# FlashMemory.net
KiCad netlist of a schematic drawn in Altium Designer
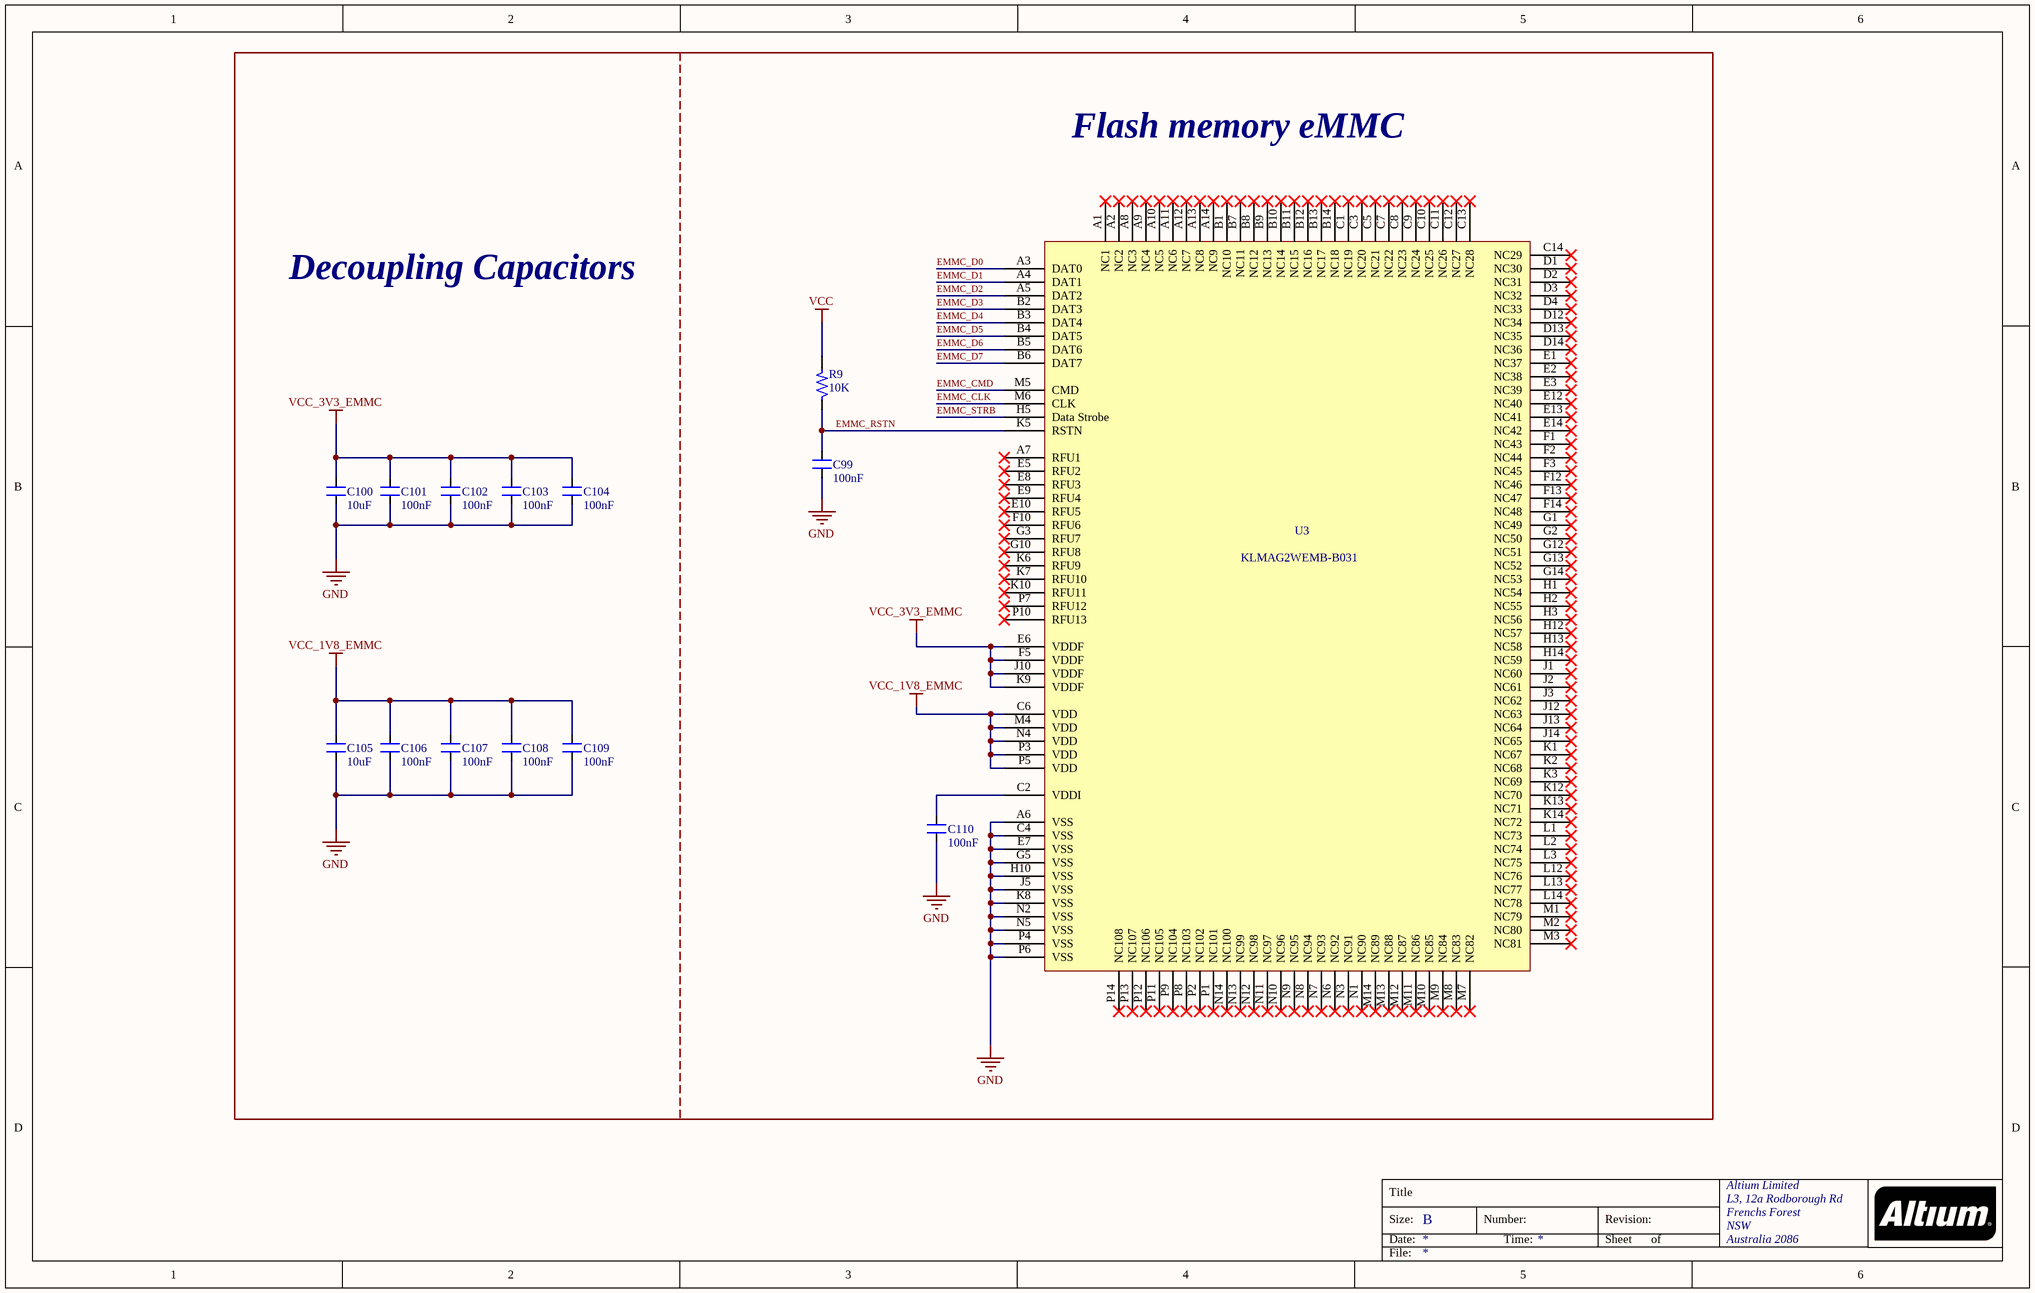
[diagram p0: FlashMemory.SchDoc]

(export (version "E")
  (design (tool "Eeschema 10.0.6"))
  (components
    (comp (ref "C99")
      (value "100nF")
      (footprint "CAP_0201")
      (description "0.1µF ±10% 25V Ceramic Capacitor X5R 0201 (0603 Metric)")
      (fields
        (field (name "MANUFACTURER") "TDK Corporation")
        (field (name "MANUFACTURER PART NUMBER") "C0603X5R1E104K030BB")
      )
      (libsource (lib "EsteemPCB_SOM_Course_intlib") (part "CAP_100nF-25V-10%-0201"))
    )
    (comp (ref "C100")
      (value "10uF")
      (footprint "CAP_0603")
      (description "10µF ±10% 25V Ceramic Capacitor X5R 0603 (1608 Metric)")
      (fields
        (field (name "MANUFACTURER") "Murata Electronics")
        (field (name "MANUFACTURER PART NUMBER") "GRM188R61E106KA73D")
      )
      (libsource (lib "EsteemPCB_SOM_Course_intlib") (part "CAP_10uF-25V-10%-0603"))
    )
    (comp (ref "C101")
      (value "100nF")
      (footprint "CAP_0201")
      (description "0.1µF ±10% 25V Ceramic Capacitor X5R 0201 (0603 Metric)")
      (fields
        (field (name "MANUFACTURER") "TDK Corporation")
        (field (name "MANUFACTURER PART NUMBER") "C0603X5R1E104K030BB")
      )
      (libsource (lib "EsteemPCB_SOM_Course_intlib") (part "CAP_100nF-25V-10%-0201"))
    )
    (comp (ref "C102")
      (value "100nF")
      (footprint "CAP_0201")
      (description "0.1µF ±10% 25V Ceramic Capacitor X5R 0201 (0603 Metric)")
      (fields
        (field (name "MANUFACTURER") "TDK Corporation")
        (field (name "MANUFACTURER PART NUMBER") "C0603X5R1E104K030BB")
      )
      (libsource (lib "EsteemPCB_SOM_Course_intlib") (part "CAP_100nF-25V-10%-0201"))
    )
    (comp (ref "C103")
      (value "100nF")
      (footprint "CAP_0201")
      (description "0.1µF ±10% 25V Ceramic Capacitor X5R 0201 (0603 Metric)")
      (fields
        (field (name "MANUFACTURER") "TDK Corporation")
        (field (name "MANUFACTURER PART NUMBER") "C0603X5R1E104K030BB")
      )
      (libsource (lib "EsteemPCB_SOM_Course_intlib") (part "CAP_100nF-25V-10%-0201"))
    )
    (comp (ref "C104")
      (value "100nF")
      (footprint "CAP_0201")
      (description "0.1µF ±10% 25V Ceramic Capacitor X5R 0201 (0603 Metric)")
      (fields
        (field (name "MANUFACTURER") "TDK Corporation")
        (field (name "MANUFACTURER PART NUMBER") "C0603X5R1E104K030BB")
      )
      (libsource (lib "EsteemPCB_SOM_Course_intlib") (part "CAP_100nF-25V-10%-0201"))
    )
    (comp (ref "C105")
      (value "10uF")
      (footprint "CAP_0603")
      (description "10µF ±10% 25V Ceramic Capacitor X5R 0603 (1608 Metric)")
      (fields
        (field (name "MANUFACTURER") "Murata Electronics")
        (field (name "MANUFACTURER PART NUMBER") "GRM188R61E106KA73D")
      )
      (libsource (lib "EsteemPCB_SOM_Course_intlib") (part "CAP_10uF-25V-10%-0603"))
    )
    (comp (ref "C106")
      (value "100nF")
      (footprint "CAP_0201")
      (description "0.1µF ±10% 25V Ceramic Capacitor X5R 0201 (0603 Metric)")
      (fields
        (field (name "MANUFACTURER") "TDK Corporation")
        (field (name "MANUFACTURER PART NUMBER") "C0603X5R1E104K030BB")
      )
      (libsource (lib "EsteemPCB_SOM_Course_intlib") (part "CAP_100nF-25V-10%-0201"))
    )
    (comp (ref "C107")
      (value "100nF")
      (footprint "CAP_0201")
      (description "0.1µF ±10% 25V Ceramic Capacitor X5R 0201 (0603 Metric)")
      (fields
        (field (name "MANUFACTURER") "TDK Corporation")
        (field (name "MANUFACTURER PART NUMBER") "C0603X5R1E104K030BB")
      )
      (libsource (lib "EsteemPCB_SOM_Course_intlib") (part "CAP_100nF-25V-10%-0201"))
    )
    (comp (ref "C108")
      (value "100nF")
      (footprint "CAP_0201")
      (description "0.1µF ±10% 25V Ceramic Capacitor X5R 0201 (0603 Metric)")
      (fields
        (field (name "MANUFACTURER") "TDK Corporation")
        (field (name "MANUFACTURER PART NUMBER") "C0603X5R1E104K030BB")
      )
      (libsource (lib "EsteemPCB_SOM_Course_intlib") (part "CAP_100nF-25V-10%-0201"))
    )
    (comp (ref "C109")
      (value "100nF")
      (footprint "CAP_0201")
      (description "0.1µF ±10% 25V Ceramic Capacitor X5R 0201 (0603 Metric)")
      (fields
        (field (name "MANUFACTURER") "TDK Corporation")
        (field (name "MANUFACTURER PART NUMBER") "C0603X5R1E104K030BB")
      )
      (libsource (lib "EsteemPCB_SOM_Course_intlib") (part "CAP_100nF-25V-10%-0201"))
    )
    (comp (ref "C110")
      (value "100nF")
      (footprint "CAP_0201")
      (description "0.1µF ±10% 25V Ceramic Capacitor X5R 0201 (0603 Metric)")
      (fields
        (field (name "MANUFACTURER") "TDK Corporation")
        (field (name "MANUFACTURER PART NUMBER") "C0603X5R1E104K030BB")
      )
      (libsource (lib "EsteemPCB_SOM_Course_intlib") (part "CAP_100nF-25V-10%-0201"))
    )
    (comp (ref "R9")
      (value "10K")
      (footprint "RES_0201")
      (description "10 kOhms ±1% 0.05W, 1/20W Chip Resistor 0201 (0603 Metric) Thick Film")
      (fields
        (field (name "MANUFACTURER") "Stackpole Electronics Inc")
        (field (name "MANUFACTURER PART NUMBER") "RMCF0201FT10K0")
      )
      (libsource (lib "EsteemPCB_SOM_Course_intlib") (part "RES_10K-0.05W-1%-0201"))
    )
    (comp (ref "U3")
      (value "KLMAG2WEMB-B031")
      (footprint "BGA153C50P14X14_1150X1300X70")
      (description "16GB NAND Flash Memory")
      (fields (field (name "MANUFACTURER") "Samsung Electronics"))
      (libsource (lib "EsteemPCB_SOM_Course_intlib") (part "IC_KLMAG2WEMB-B031"))
    )
  )
  (nets
    (net (code "1") (name "/EMMC_CLK") (class "Default")
      (node (ref "U3") (pin "M6") (pinfunction "CLK_M6") (pintype "passive"))
    )
    (net (code "2") (name "/EMMC_CMD") (class "Default")
      (node (ref "U3") (pin "M5") (pinfunction "CMD_M5") (pintype "passive"))
    )
    (net (code "3") (name "/EMMC_D0") (class "Default")
      (node (ref "U3") (pin "A3") (pinfunction "DAT0_A3") (pintype "passive"))
    )
    (net (code "4") (name "/EMMC_D1") (class "Default")
      (node (ref "U3") (pin "A4") (pinfunction "DAT1_A4") (pintype "passive"))
    )
    (net (code "5") (name "/EMMC_D2") (class "Default")
      (node (ref "U3") (pin "A5") (pinfunction "DAT2_A5") (pintype "passive"))
    )
    (net (code "6") (name "/EMMC_D3") (class "Default")
      (node (ref "U3") (pin "B2") (pinfunction "DAT3_B2") (pintype "passive"))
    )
    (net (code "7") (name "/EMMC_D4") (class "Default")
      (node (ref "U3") (pin "B3") (pinfunction "DAT4_B3") (pintype "passive"))
    )
    (net (code "8") (name "/EMMC_D5") (class "Default")
      (node (ref "U3") (pin "B4") (pinfunction "DAT5_B4") (pintype "passive"))
    )
    (net (code "9") (name "/EMMC_D6") (class "Default")
      (node (ref "U3") (pin "B5") (pinfunction "DAT6_B5") (pintype "passive"))
    )
    (net (code "10") (name "/EMMC_D7") (class "Default")
      (node (ref "U3") (pin "B6") (pinfunction "DAT7_B6") (pintype "passive"))
    )
    (net (code "11") (name "/EMMC_RSTN") (class "Default")
      (node (ref "C99") (pin "2") (pinfunction "2_2") (pintype "passive"))
      (node (ref "R9") (pin "1") (pinfunction "1_1") (pintype "passive"))
      (node (ref "U3") (pin "K5") (pinfunction "RSTN_K5") (pintype "passive"))
    )
    (net (code "12") (name "/EMMC_STRB") (class "Default")
      (node (ref "U3") (pin "H5") (pinfunction "Data_Strobe_H5") (pintype "passive"))
    )
    (net (code "13") (name "GND") (class "Default")
      (node (ref "C100") (pin "1") (pinfunction "1_1") (pintype "passive"))
      (node (ref "C101") (pin "1") (pinfunction "1_1") (pintype "passive"))
      (node (ref "C102") (pin "1") (pinfunction "1_1") (pintype "passive"))
      (node (ref "C103") (pin "1") (pinfunction "1_1") (pintype "passive"))
      (node (ref "C104") (pin "1") (pinfunction "1_1") (pintype "passive"))
      (node (ref "C105") (pin "1") (pinfunction "1_1") (pintype "passive"))
      (node (ref "C106") (pin "1") (pinfunction "1_1") (pintype "passive"))
      (node (ref "C107") (pin "1") (pinfunction "1_1") (pintype "passive"))
      (node (ref "C108") (pin "1") (pinfunction "1_1") (pintype "passive"))
      (node (ref "C109") (pin "1") (pinfunction "1_1") (pintype "passive"))
      (node (ref "C110") (pin "1") (pinfunction "1_1") (pintype "passive"))
      (node (ref "C99") (pin "1") (pinfunction "1_1") (pintype "passive"))
      (node (ref "U3") (pin "A6") (pinfunction "VSS_A6") (pintype "passive"))
      (node (ref "U3") (pin "C4") (pinfunction "VSS_C4") (pintype "passive"))
      (node (ref "U3") (pin "E7") (pinfunction "VSS_E7") (pintype "passive"))
      (node (ref "U3") (pin "G5") (pinfunction "VSS_G5") (pintype "passive"))
      (node (ref "U3") (pin "H10") (pinfunction "VSS_H10") (pintype "passive"))
      (node (ref "U3") (pin "J5") (pinfunction "VSS_J5") (pintype "passive"))
      (node (ref "U3") (pin "K8") (pinfunction "VSS_K8") (pintype "passive"))
      (node (ref "U3") (pin "N2") (pinfunction "VSS_N2") (pintype "passive"))
      (node (ref "U3") (pin "N5") (pinfunction "VSS_N5") (pintype "passive"))
      (node (ref "U3") (pin "P4") (pinfunction "VSS_P4") (pintype "passive"))
      (node (ref "U3") (pin "P6") (pinfunction "VSS_P6") (pintype "passive"))
    )
    (net (code "14") (name "Net-(U3-VDDI)") (class "Default")
      (node (ref "C110") (pin "2") (pinfunction "2_2") (pintype "passive"))
      (node (ref "U3") (pin "C2") (pinfunction "VDDI_C2") (pintype "passive"))
    )
    (net (code "15") (name "VCC") (class "Default")
      (node (ref "R9") (pin "2") (pinfunction "2_2") (pintype "passive"))
    )
    (net (code "16") (name "VCC_1V8_EMMC") (class "Default")
      (node (ref "C105") (pin "2") (pinfunction "2_2") (pintype "passive"))
      (node (ref "C106") (pin "2") (pinfunction "2_2") (pintype "passive"))
      (node (ref "C107") (pin "2") (pinfunction "2_2") (pintype "passive"))
      (node (ref "C108") (pin "2") (pinfunction "2_2") (pintype "passive"))
      (node (ref "C109") (pin "2") (pinfunction "2_2") (pintype "passive"))
      (node (ref "U3") (pin "C6") (pinfunction "VDD_C6") (pintype "passive"))
      (node (ref "U3") (pin "M4") (pinfunction "VDD_M4") (pintype "passive"))
      (node (ref "U3") (pin "N4") (pinfunction "VDD_N4") (pintype "passive"))
      (node (ref "U3") (pin "P3") (pinfunction "VDD_P3") (pintype "passive"))
      (node (ref "U3") (pin "P5") (pinfunction "VDD_P5") (pintype "passive"))
    )
    (net (code "17") (name "VCC_3V3_EMMC") (class "Default")
      (node (ref "C100") (pin "2") (pinfunction "2_2") (pintype "passive"))
      (node (ref "C101") (pin "2") (pinfunction "2_2") (pintype "passive"))
      (node (ref "C102") (pin "2") (pinfunction "2_2") (pintype "passive"))
      (node (ref "C103") (pin "2") (pinfunction "2_2") (pintype "passive"))
      (node (ref "C104") (pin "2") (pinfunction "2_2") (pintype "passive"))
      (node (ref "U3") (pin "E6") (pinfunction "VDDF_E6") (pintype "passive"))
      (node (ref "U3") (pin "F5") (pinfunction "VDDF_F5") (pintype "passive"))
      (node (ref "U3") (pin "J10") (pinfunction "VDDF_J10") (pintype "passive"))
      (node (ref "U3") (pin "K9") (pinfunction "VDDF_K9") (pintype "passive"))
    )
    (net (code "18") (name "unconnected-(U3-NC1-PadA1)") (class "Default")
      (node (ref "U3") (pin "A1") (pinfunction "NC1_A1") (pintype "passive+no_connect"))
    )
    (net (code "19") (name "unconnected-(U3-NC2-PadA2)") (class "Default")
      (node (ref "U3") (pin "A2") (pinfunction "NC2_A2") (pintype "passive+no_connect"))
    )
    (net (code "20") (name "unconnected-(U3-NC3-PadA8)") (class "Default")
      (node (ref "U3") (pin "A8") (pinfunction "NC3_A8") (pintype "passive+no_connect"))
    )
    (net (code "21") (name "unconnected-(U3-NC4-PadA9)") (class "Default")
      (node (ref "U3") (pin "A9") (pinfunction "NC4_A9") (pintype "passive+no_connect"))
    )
    (net (code "22") (name "unconnected-(U3-NC5-PadA10)") (class "Default")
      (node (ref "U3") (pin "A10") (pinfunction "NC5_A10") (pintype "passive+no_connect"))
    )
    (net (code "23") (name "unconnected-(U3-NC6-PadA11)") (class "Default")
      (node (ref "U3") (pin "A11") (pinfunction "NC6_A11") (pintype "passive+no_connect"))
    )
    (net (code "24") (name "unconnected-(U3-NC7-PadA12)") (class "Default")
      (node (ref "U3") (pin "A12") (pinfunction "NC7_A12") (pintype "passive+no_connect"))
    )
    (net (code "25") (name "unconnected-(U3-NC8-PadA13)") (class "Default")
      (node (ref "U3") (pin "A13") (pinfunction "NC8_A13") (pintype "passive+no_connect"))
    )
    (net (code "26") (name "unconnected-(U3-NC9-PadA14)") (class "Default")
      (node (ref "U3") (pin "A14") (pinfunction "NC9_A14") (pintype "passive+no_connect"))
    )
    (net (code "27") (name "unconnected-(U3-NC10-PadB1)") (class "Default")
      (node (ref "U3") (pin "B1") (pinfunction "NC10_B1") (pintype "passive+no_connect"))
    )
    (net (code "28") (name "unconnected-(U3-NC11-PadB7)") (class "Default")
      (node (ref "U3") (pin "B7") (pinfunction "NC11_B7") (pintype "passive+no_connect"))
    )
    (net (code "29") (name "unconnected-(U3-NC12-PadB8)") (class "Default")
      (node (ref "U3") (pin "B8") (pinfunction "NC12_B8") (pintype "passive+no_connect"))
    )
    (net (code "30") (name "unconnected-(U3-NC13-PadB9)") (class "Default")
      (node (ref "U3") (pin "B9") (pinfunction "NC13_B9") (pintype "passive+no_connect"))
    )
    (net (code "31") (name "unconnected-(U3-NC14-PadB10)") (class "Default")
      (node (ref "U3") (pin "B10") (pinfunction "NC14_B10") (pintype "passive+no_connect"))
    )
    (net (code "32") (name "unconnected-(U3-NC15-PadB11)") (class "Default")
      (node (ref "U3") (pin "B11") (pinfunction "NC15_B11") (pintype "passive+no_connect"))
    )
    (net (code "33") (name "unconnected-(U3-NC16-PadB12)") (class "Default")
      (node (ref "U3") (pin "B12") (pinfunction "NC16_B12") (pintype "passive+no_connect"))
    )
    (net (code "34") (name "unconnected-(U3-NC17-PadB13)") (class "Default")
      (node (ref "U3") (pin "B13") (pinfunction "NC17_B13") (pintype "passive+no_connect"))
    )
    (net (code "35") (name "unconnected-(U3-NC18-PadB14)") (class "Default")
      (node (ref "U3") (pin "B14") (pinfunction "NC18_B14") (pintype "passive+no_connect"))
    )
    (net (code "36") (name "unconnected-(U3-NC19-PadC1)") (class "Default")
      (node (ref "U3") (pin "C1") (pinfunction "NC19_C1") (pintype "passive+no_connect"))
    )
    (net (code "37") (name "unconnected-(U3-NC20-PadC3)") (class "Default")
      (node (ref "U3") (pin "C3") (pinfunction "NC20_C3") (pintype "passive+no_connect"))
    )
    (net (code "38") (name "unconnected-(U3-NC21-PadC5)") (class "Default")
      (node (ref "U3") (pin "C5") (pinfunction "NC21_C5") (pintype "passive+no_connect"))
    )
    (net (code "39") (name "unconnected-(U3-NC22-PadC7)") (class "Default")
      (node (ref "U3") (pin "C7") (pinfunction "NC22_C7") (pintype "passive+no_connect"))
    )
    (net (code "40") (name "unconnected-(U3-NC23-PadC8)") (class "Default")
      (node (ref "U3") (pin "C8") (pinfunction "NC23_C8") (pintype "passive+no_connect"))
    )
    (net (code "41") (name "unconnected-(U3-NC24-PadC9)") (class "Default")
      (node (ref "U3") (pin "C9") (pinfunction "NC24_C9") (pintype "passive+no_connect"))
    )
    (net (code "42") (name "unconnected-(U3-NC25-PadC10)") (class "Default")
      (node (ref "U3") (pin "C10") (pinfunction "NC25_C10") (pintype "passive+no_connect"))
    )
    (net (code "43") (name "unconnected-(U3-NC26-PadC11)") (class "Default")
      (node (ref "U3") (pin "C11") (pinfunction "NC26_C11") (pintype "passive+no_connect"))
    )
    (net (code "44") (name "unconnected-(U3-NC27-PadC12)") (class "Default")
      (node (ref "U3") (pin "C12") (pinfunction "NC27_C12") (pintype "passive+no_connect"))
    )
    (net (code "45") (name "unconnected-(U3-NC28-PadC13)") (class "Default")
      (node (ref "U3") (pin "C13") (pinfunction "NC28_C13") (pintype "passive+no_connect"))
    )
    (net (code "46") (name "unconnected-(U3-NC29-PadC14)") (class "Default")
      (node (ref "U3") (pin "C14") (pinfunction "NC29_C14") (pintype "passive+no_connect"))
    )
    (net (code "47") (name "unconnected-(U3-NC30-PadD1)") (class "Default")
      (node (ref "U3") (pin "D1") (pinfunction "NC30_D1") (pintype "passive+no_connect"))
    )
    (net (code "48") (name "unconnected-(U3-NC31-PadD2)") (class "Default")
      (node (ref "U3") (pin "D2") (pinfunction "NC31_D2") (pintype "passive+no_connect"))
    )
    (net (code "49") (name "unconnected-(U3-NC32-PadD3)") (class "Default")
      (node (ref "U3") (pin "D3") (pinfunction "NC32_D3") (pintype "passive+no_connect"))
    )
    (net (code "50") (name "unconnected-(U3-NC33-PadD4)") (class "Default")
      (node (ref "U3") (pin "D4") (pinfunction "NC33_D4") (pintype "passive+no_connect"))
    )
    (net (code "51") (name "unconnected-(U3-NC34-PadD12)") (class "Default")
      (node (ref "U3") (pin "D12") (pinfunction "NC34_D12") (pintype "passive+no_connect"))
    )
    (net (code "52") (name "unconnected-(U3-NC35-PadD13)") (class "Default")
      (node (ref "U3") (pin "D13") (pinfunction "NC35_D13") (pintype "passive+no_connect"))
    )
    (net (code "53") (name "unconnected-(U3-NC36-PadD14)") (class "Default")
      (node (ref "U3") (pin "D14") (pinfunction "NC36_D14") (pintype "passive+no_connect"))
    )
    (net (code "54") (name "unconnected-(U3-NC37-PadE1)") (class "Default")
      (node (ref "U3") (pin "E1") (pinfunction "NC37_E1") (pintype "passive+no_connect"))
    )
    (net (code "55") (name "unconnected-(U3-NC38-PadE2)") (class "Default")
      (node (ref "U3") (pin "E2") (pinfunction "NC38_E2") (pintype "passive+no_connect"))
    )
    (net (code "56") (name "unconnected-(U3-NC39-PadE3)") (class "Default")
      (node (ref "U3") (pin "E3") (pinfunction "NC39_E3") (pintype "passive+no_connect"))
    )
    (net (code "57") (name "unconnected-(U3-NC40-PadE12)") (class "Default")
      (node (ref "U3") (pin "E12") (pinfunction "NC40_E12") (pintype "passive+no_connect"))
    )
    (net (code "58") (name "unconnected-(U3-NC41-PadE13)") (class "Default")
      (node (ref "U3") (pin "E13") (pinfunction "NC41_E13") (pintype "passive+no_connect"))
    )
    (net (code "59") (name "unconnected-(U3-NC42-PadE14)") (class "Default")
      (node (ref "U3") (pin "E14") (pinfunction "NC42_E14") (pintype "passive+no_connect"))
    )
    (net (code "60") (name "unconnected-(U3-NC43-PadF1)") (class "Default")
      (node (ref "U3") (pin "F1") (pinfunction "NC43_F1") (pintype "passive+no_connect"))
    )
    (net (code "61") (name "unconnected-(U3-NC44-PadF2)") (class "Default")
      (node (ref "U3") (pin "F2") (pinfunction "NC44_F2") (pintype "passive+no_connect"))
    )
    (net (code "62") (name "unconnected-(U3-NC45-PadF3)") (class "Default")
      (node (ref "U3") (pin "F3") (pinfunction "NC45_F3") (pintype "passive+no_connect"))
    )
    (net (code "63") (name "unconnected-(U3-NC46-PadF12)") (class "Default")
      (node (ref "U3") (pin "F12") (pinfunction "NC46_F12") (pintype "passive+no_connect"))
    )
    (net (code "64") (name "unconnected-(U3-NC47-PadF13)") (class "Default")
      (node (ref "U3") (pin "F13") (pinfunction "NC47_F13") (pintype "passive+no_connect"))
    )
    (net (code "65") (name "unconnected-(U3-NC48-PadF14)") (class "Default")
      (node (ref "U3") (pin "F14") (pinfunction "NC48_F14") (pintype "passive+no_connect"))
    )
    (net (code "66") (name "unconnected-(U3-NC49-PadG1)") (class "Default")
      (node (ref "U3") (pin "G1") (pinfunction "NC49_G1") (pintype "passive+no_connect"))
    )
    (net (code "67") (name "unconnected-(U3-NC50-PadG2)") (class "Default")
      (node (ref "U3") (pin "G2") (pinfunction "NC50_G2") (pintype "passive+no_connect"))
    )
    (net (code "68") (name "unconnected-(U3-NC51-PadG12)") (class "Default")
      (node (ref "U3") (pin "G12") (pinfunction "NC51_G12") (pintype "passive+no_connect"))
    )
    (net (code "69") (name "unconnected-(U3-NC52-PadG13)") (class "Default")
      (node (ref "U3") (pin "G13") (pinfunction "NC52_G13") (pintype "passive+no_connect"))
    )
    (net (code "70") (name "unconnected-(U3-NC53-PadG14)") (class "Default")
      (node (ref "U3") (pin "G14") (pinfunction "NC53_G14") (pintype "passive+no_connect"))
    )
    (net (code "71") (name "unconnected-(U3-NC54-PadH1)") (class "Default")
      (node (ref "U3") (pin "H1") (pinfunction "NC54_H1") (pintype "passive+no_connect"))
    )
    (net (code "72") (name "unconnected-(U3-NC55-PadH2)") (class "Default")
      (node (ref "U3") (pin "H2") (pinfunction "NC55_H2") (pintype "passive+no_connect"))
    )
    (net (code "73") (name "unconnected-(U3-NC56-PadH3)") (class "Default")
      (node (ref "U3") (pin "H3") (pinfunction "NC56_H3") (pintype "passive+no_connect"))
    )
    (net (code "74") (name "unconnected-(U3-NC57-PadH12)") (class "Default")
      (node (ref "U3") (pin "H12") (pinfunction "NC57_H12") (pintype "passive+no_connect"))
    )
    (net (code "75") (name "unconnected-(U3-NC58-PadH13)") (class "Default")
      (node (ref "U3") (pin "H13") (pinfunction "NC58_H13") (pintype "passive+no_connect"))
    )
    (net (code "76") (name "unconnected-(U3-NC59-PadH14)") (class "Default")
      (node (ref "U3") (pin "H14") (pinfunction "NC59_H14") (pintype "passive+no_connect"))
    )
    (net (code "77") (name "unconnected-(U3-NC60-PadJ1)") (class "Default")
      (node (ref "U3") (pin "J1") (pinfunction "NC60_J1") (pintype "passive+no_connect"))
    )
    (net (code "78") (name "unconnected-(U3-NC61-PadJ2)") (class "Default")
      (node (ref "U3") (pin "J2") (pinfunction "NC61_J2") (pintype "passive+no_connect"))
    )
    (net (code "79") (name "unconnected-(U3-NC62-PadJ3)") (class "Default")
      (node (ref "U3") (pin "J3") (pinfunction "NC62_J3") (pintype "passive+no_connect"))
    )
    (net (code "80") (name "unconnected-(U3-NC63-PadJ12)") (class "Default")
      (node (ref "U3") (pin "J12") (pinfunction "NC63_J12") (pintype "passive+no_connect"))
    )
    (net (code "81") (name "unconnected-(U3-NC64-PadJ13)") (class "Default")
      (node (ref "U3") (pin "J13") (pinfunction "NC64_J13") (pintype "passive+no_connect"))
    )
    (net (code "82") (name "unconnected-(U3-NC65-PadJ14)") (class "Default")
      (node (ref "U3") (pin "J14") (pinfunction "NC65_J14") (pintype "passive+no_connect"))
    )
    (net (code "83") (name "unconnected-(U3-NC67-PadK1)") (class "Default")
      (node (ref "U3") (pin "K1") (pinfunction "NC67_K1") (pintype "passive+no_connect"))
    )
    (net (code "84") (name "unconnected-(U3-NC68-PadK2)") (class "Default")
      (node (ref "U3") (pin "K2") (pinfunction "NC68_K2") (pintype "passive+no_connect"))
    )
    (net (code "85") (name "unconnected-(U3-NC69-PadK3)") (class "Default")
      (node (ref "U3") (pin "K3") (pinfunction "NC69_K3") (pintype "passive+no_connect"))
    )
    (net (code "86") (name "unconnected-(U3-NC70-PadK12)") (class "Default")
      (node (ref "U3") (pin "K12") (pinfunction "NC70_K12") (pintype "passive+no_connect"))
    )
    (net (code "87") (name "unconnected-(U3-NC71-PadK13)") (class "Default")
      (node (ref "U3") (pin "K13") (pinfunction "NC71_K13") (pintype "passive+no_connect"))
    )
    (net (code "88") (name "unconnected-(U3-NC72-PadK14)") (class "Default")
      (node (ref "U3") (pin "K14") (pinfunction "NC72_K14") (pintype "passive+no_connect"))
    )
    (net (code "89") (name "unconnected-(U3-NC73-PadL1)") (class "Default")
      (node (ref "U3") (pin "L1") (pinfunction "NC73_L1") (pintype "passive+no_connect"))
    )
    (net (code "90") (name "unconnected-(U3-NC74-PadL2)") (class "Default")
      (node (ref "U3") (pin "L2") (pinfunction "NC74_L2") (pintype "passive+no_connect"))
    )
    (net (code "91") (name "unconnected-(U3-NC75-PadL3)") (class "Default")
      (node (ref "U3") (pin "L3") (pinfunction "NC75_L3") (pintype "passive+no_connect"))
    )
    (net (code "92") (name "unconnected-(U3-NC76-PadL12)") (class "Default")
      (node (ref "U3") (pin "L12") (pinfunction "NC76_L12") (pintype "passive+no_connect"))
    )
    (net (code "93") (name "unconnected-(U3-NC77-PadL13)") (class "Default")
      (node (ref "U3") (pin "L13") (pinfunction "NC77_L13") (pintype "passive+no_connect"))
    )
    (net (code "94") (name "unconnected-(U3-NC78-PadL14)") (class "Default")
      (node (ref "U3") (pin "L14") (pinfunction "NC78_L14") (pintype "passive+no_connect"))
    )
    (net (code "95") (name "unconnected-(U3-NC79-PadM1)") (class "Default")
      (node (ref "U3") (pin "M1") (pinfunction "NC79_M1") (pintype "passive+no_connect"))
    )
    (net (code "96") (name "unconnected-(U3-NC80-PadM2)") (class "Default")
      (node (ref "U3") (pin "M2") (pinfunction "NC80_M2") (pintype "passive+no_connect"))
    )
    (net (code "97") (name "unconnected-(U3-NC81-PadM3)") (class "Default")
      (node (ref "U3") (pin "M3") (pinfunction "NC81_M3") (pintype "passive+no_connect"))
    )
    (net (code "98") (name "unconnected-(U3-NC82-PadM7)") (class "Default")
      (node (ref "U3") (pin "M7") (pinfunction "NC82_M7") (pintype "passive+no_connect"))
    )
    (net (code "99") (name "unconnected-(U3-NC83-PadM8)") (class "Default")
      (node (ref "U3") (pin "M8") (pinfunction "NC83_M8") (pintype "passive+no_connect"))
    )
    (net (code "100") (name "unconnected-(U3-NC84-PadM9)") (class "Default")
      (node (ref "U3") (pin "M9") (pinfunction "NC84_M9") (pintype "passive+no_connect"))
    )
    (net (code "101") (name "unconnected-(U3-NC85-PadM10)") (class "Default")
      (node (ref "U3") (pin "M10") (pinfunction "NC85_M10") (pintype "passive+no_connect"))
    )
    (net (code "102") (name "unconnected-(U3-NC86-PadM11)") (class "Default")
      (node (ref "U3") (pin "M11") (pinfunction "NC86_M11") (pintype "passive+no_connect"))
    )
    (net (code "103") (name "unconnected-(U3-NC87-PadM12)") (class "Default")
      (node (ref "U3") (pin "M12") (pinfunction "NC87_M12") (pintype "passive+no_connect"))
    )
    (net (code "104") (name "unconnected-(U3-NC88-PadM13)") (class "Default")
      (node (ref "U3") (pin "M13") (pinfunction "NC88_M13") (pintype "passive+no_connect"))
    )
    (net (code "105") (name "unconnected-(U3-NC89-PadM14)") (class "Default")
      (node (ref "U3") (pin "M14") (pinfunction "NC89_M14") (pintype "passive+no_connect"))
    )
    (net (code "106") (name "unconnected-(U3-NC90-PadN1)") (class "Default")
      (node (ref "U3") (pin "N1") (pinfunction "NC90_N1") (pintype "passive+no_connect"))
    )
    (net (code "107") (name "unconnected-(U3-NC91-PadN3)") (class "Default")
      (node (ref "U3") (pin "N3") (pinfunction "NC91_N3") (pintype "passive+no_connect"))
    )
    (net (code "108") (name "unconnected-(U3-NC92-PadN6)") (class "Default")
      (node (ref "U3") (pin "N6") (pinfunction "NC92_N6") (pintype "passive+no_connect"))
    )
    (net (code "109") (name "unconnected-(U3-NC93-PadN7)") (class "Default")
      (node (ref "U3") (pin "N7") (pinfunction "NC93_N7") (pintype "passive+no_connect"))
    )
    (net (code "110") (name "unconnected-(U3-NC94-PadN8)") (class "Default")
      (node (ref "U3") (pin "N8") (pinfunction "NC94_N8") (pintype "passive+no_connect"))
    )
    (net (code "111") (name "unconnected-(U3-NC95-PadN9)") (class "Default")
      (node (ref "U3") (pin "N9") (pinfunction "NC95_N9") (pintype "passive+no_connect"))
    )
    (net (code "112") (name "unconnected-(U3-NC96-PadN10)") (class "Default")
      (node (ref "U3") (pin "N10") (pinfunction "NC96_N10") (pintype "passive+no_connect"))
    )
    (net (code "113") (name "unconnected-(U3-NC97-PadN11)") (class "Default")
      (node (ref "U3") (pin "N11") (pinfunction "NC97_N11") (pintype "passive+no_connect"))
    )
    (net (code "114") (name "unconnected-(U3-NC98-PadN12)") (class "Default")
      (node (ref "U3") (pin "N12") (pinfunction "NC98_N12") (pintype "passive+no_connect"))
    )
    (net (code "115") (name "unconnected-(U3-NC99-PadN13)") (class "Default")
      (node (ref "U3") (pin "N13") (pinfunction "NC99_N13") (pintype "passive+no_connect"))
    )
    (net (code "116") (name "unconnected-(U3-NC100-PadN14)") (class "Default")
      (node (ref "U3") (pin "N14") (pinfunction "NC100_N14") (pintype "passive+no_connect"))
    )
    (net (code "117") (name "unconnected-(U3-NC101-PadP1)") (class "Default")
      (node (ref "U3") (pin "P1") (pinfunction "NC101_P1") (pintype "passive+no_connect"))
    )
    (net (code "118") (name "unconnected-(U3-NC102-PadP2)") (class "Default")
      (node (ref "U3") (pin "P2") (pinfunction "NC102_P2") (pintype "passive+no_connect"))
    )
    (net (code "119") (name "unconnected-(U3-NC103-PadP8)") (class "Default")
      (node (ref "U3") (pin "P8") (pinfunction "NC103_P8") (pintype "passive+no_connect"))
    )
    (net (code "120") (name "unconnected-(U3-NC104-PadP9)") (class "Default")
      (node (ref "U3") (pin "P9") (pinfunction "NC104_P9") (pintype "passive+no_connect"))
    )
    (net (code "121") (name "unconnected-(U3-NC105-PadP11)") (class "Default")
      (node (ref "U3") (pin "P11") (pinfunction "NC105_P11") (pintype "passive+no_connect"))
    )
    (net (code "122") (name "unconnected-(U3-NC106-PadP12)") (class "Default")
      (node (ref "U3") (pin "P12") (pinfunction "NC106_P12") (pintype "passive+no_connect"))
    )
    (net (code "123") (name "unconnected-(U3-NC107-PadP13)") (class "Default")
      (node (ref "U3") (pin "P13") (pinfunction "NC107_P13") (pintype "passive+no_connect"))
    )
    (net (code "124") (name "unconnected-(U3-NC108-PadP14)") (class "Default")
      (node (ref "U3") (pin "P14") (pinfunction "NC108_P14") (pintype "passive+no_connect"))
    )
    (net (code "125") (name "unconnected-(U3-RFU1-PadA7)") (class "Default")
      (node (ref "U3") (pin "A7") (pinfunction "RFU1_A7") (pintype "passive+no_connect"))
    )
    (net (code "126") (name "unconnected-(U3-RFU2-PadE5)") (class "Default")
      (node (ref "U3") (pin "E5") (pinfunction "RFU2_E5") (pintype "passive+no_connect"))
    )
    (net (code "127") (name "unconnected-(U3-RFU3-PadE8)") (class "Default")
      (node (ref "U3") (pin "E8") (pinfunction "RFU3_E8") (pintype "passive+no_connect"))
    )
    (net (code "128") (name "unconnected-(U3-RFU4-PadE9)") (class "Default")
      (node (ref "U3") (pin "E9") (pinfunction "RFU4_E9") (pintype "passive+no_connect"))
    )
    (net (code "129") (name "unconnected-(U3-RFU5-PadE10)") (class "Default")
      (node (ref "U3") (pin "E10") (pinfunction "RFU5_E10") (pintype "passive+no_connect"))
    )
    (net (code "130") (name "unconnected-(U3-RFU6-PadF10)") (class "Default")
      (node (ref "U3") (pin "F10") (pinfunction "RFU6_F10") (pintype "passive+no_connect"))
    )
    (net (code "131") (name "unconnected-(U3-RFU7-PadG3)") (class "Default")
      (node (ref "U3") (pin "G3") (pinfunction "RFU7_G3") (pintype "passive+no_connect"))
    )
    (net (code "132") (name "unconnected-(U3-RFU8-PadG10)") (class "Default")
      (node (ref "U3") (pin "G10") (pinfunction "RFU8_G10") (pintype "passive+no_connect"))
    )
    (net (code "133") (name "unconnected-(U3-RFU9-PadK6)") (class "Default")
      (node (ref "U3") (pin "K6") (pinfunction "RFU9_K6") (pintype "passive+no_connect"))
    )
    (net (code "134") (name "unconnected-(U3-RFU10-PadK7)") (class "Default")
      (node (ref "U3") (pin "K7") (pinfunction "RFU10_K7") (pintype "passive+no_connect"))
    )
    (net (code "135") (name "unconnected-(U3-RFU11-PadK10)") (class "Default")
      (node (ref "U3") (pin "K10") (pinfunction "RFU11_K10") (pintype "passive+no_connect"))
    )
    (net (code "136") (name "unconnected-(U3-RFU12-PadP7)") (class "Default")
      (node (ref "U3") (pin "P7") (pinfunction "RFU12_P7") (pintype "passive+no_connect"))
    )
    (net (code "137") (name "unconnected-(U3-RFU13-PadP10)") (class "Default")
      (node (ref "U3") (pin "P10") (pinfunction "RFU13_P10") (pintype "passive+no_connect"))
    )
  )
)
